# power.net
KiCad netlist of a schematic drawn in Altium Designer
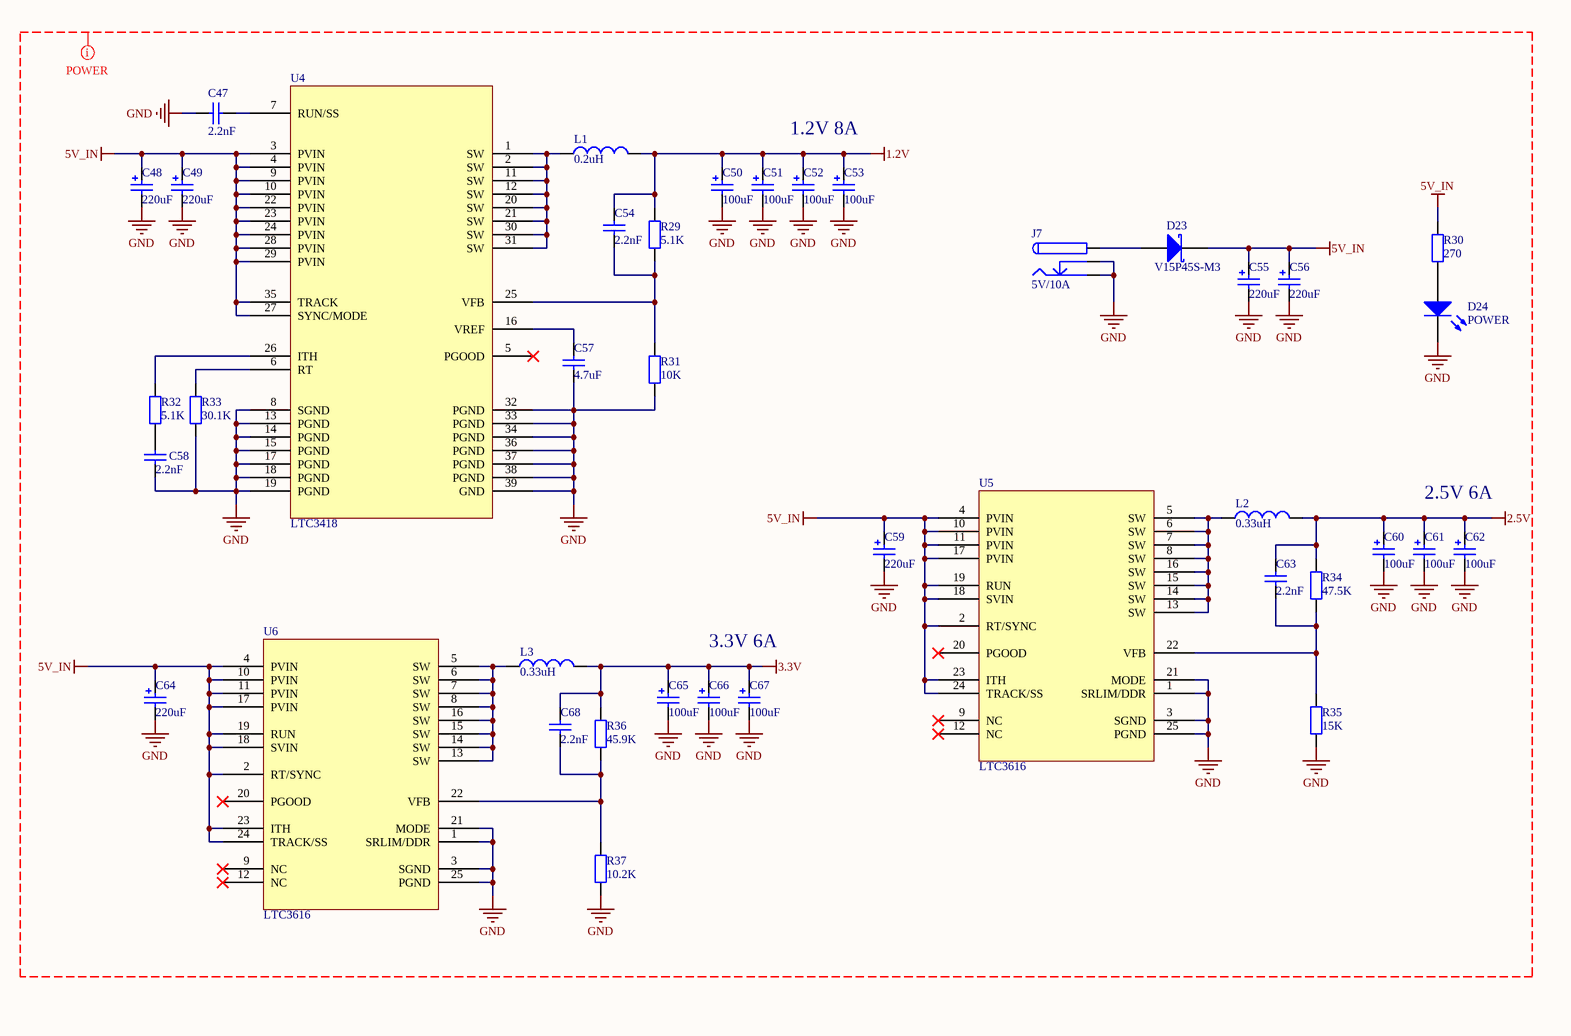
[diagram p0: power.SchDoc]

(export (version "E")
  (design (tool "Eeschema 10.0.6"))
  (components
    (comp (ref "C47")
      (value "2.2nF")
      (footprint "1608[0603]")
      (description "Capacitor")
      (fields (field (name "Comment") "Cap") (field (name "PUBLISHER") "Altium Limited"))
      (libsource (lib "Miscellaneous Devices") (part "Cap"))
    )
    (comp (ref "C48")
      (value "220uF")
      (footprint "C220_POLARIZED")
      (description "Polarized Capacitor (Axial)")
      (fields (field (name "Comment") "Cap Pol2") (field (name "PUBLISHER") "Altium Limited"))
      (libsource (lib "Miscellaneous Devices") (part "Cap Pol2"))
    )
    (comp (ref "C49")
      (value "220uF")
      (footprint "C220_POLARIZED")
      (description "Polarized Capacitor (Axial)")
      (fields (field (name "Comment") "Cap Pol2") (field (name "PUBLISHER") "Altium Limited"))
      (libsource (lib "Miscellaneous Devices") (part "Cap Pol2"))
    )
    (comp (ref "C50")
      (value "100uF")
      (footprint "C1206_POLARIZED")
      (description "Polarized Capacitor (Axial)")
      (fields (field (name "Comment") "Cap Pol2") (field (name "PUBLISHER") "Altium Limited"))
      (libsource (lib "Miscellaneous Devices") (part "Cap Pol2"))
    )
    (comp (ref "C51")
      (value "100uF")
      (footprint "C1206_POLARIZED")
      (description "Polarized Capacitor (Axial)")
      (fields (field (name "Comment") "Cap Pol2") (field (name "PUBLISHER") "Altium Limited"))
      (libsource (lib "Miscellaneous Devices") (part "Cap Pol2"))
    )
    (comp (ref "C52")
      (value "100uF")
      (footprint "C1206_POLARIZED")
      (description "Polarized Capacitor (Axial)")
      (fields (field (name "Comment") "Cap Pol2") (field (name "PUBLISHER") "Altium Limited"))
      (libsource (lib "Miscellaneous Devices") (part "Cap Pol2"))
    )
    (comp (ref "C53")
      (value "100uF")
      (footprint "C1206_POLARIZED")
      (description "Polarized Capacitor (Axial)")
      (fields (field (name "Comment") "Cap Pol2") (field (name "PUBLISHER") "Altium Limited"))
      (libsource (lib "Miscellaneous Devices") (part "Cap Pol2"))
    )
    (comp (ref "C54")
      (value "2.2nF")
      (footprint "1608[0603]")
      (description "Capacitor")
      (fields (field (name "Comment") "Cap") (field (name "PUBLISHER") "Altium Limited"))
      (libsource (lib "Miscellaneous Devices") (part "Cap"))
    )
    (comp (ref "C55")
      (value "220uF")
      (footprint "C220_POLARIZED")
      (description "Polarized Capacitor (Axial)")
      (fields (field (name "Comment") "Cap Pol2") (field (name "PUBLISHER") "Altium Limited"))
      (libsource (lib "Miscellaneous Devices") (part "Cap Pol2"))
    )
    (comp (ref "C56")
      (value "220uF")
      (footprint "C220_POLARIZED")
      (description "Polarized Capacitor (Axial)")
      (fields (field (name "Comment") "Cap Pol2") (field (name "PUBLISHER") "Altium Limited"))
      (libsource (lib "Miscellaneous Devices") (part "Cap Pol2"))
    )
    (comp (ref "C57")
      (value "4.7uF")
      (footprint "C0805")
      (description "Capacitor")
      (fields (field (name "Comment") "Cap") (field (name "PUBLISHER") "Altium Limited"))
      (libsource (lib "Miscellaneous Devices") (part "Cap"))
    )
    (comp (ref "C58")
      (value "2.2nF")
      (footprint "1608[0603]")
      (description "Capacitor")
      (fields (field (name "Comment") "Cap") (field (name "PUBLISHER") "Altium Limited"))
      (libsource (lib "Miscellaneous Devices") (part "Cap"))
    )
    (comp (ref "C59")
      (value "220uF")
      (footprint "C220_POLARIZED")
      (description "Polarized Capacitor (Axial)")
      (fields (field (name "Comment") "Cap Pol2") (field (name "PUBLISHER") "Altium Limited"))
      (libsource (lib "Miscellaneous Devices") (part "Cap Pol2"))
    )
    (comp (ref "C60")
      (value "100uF")
      (footprint "C1206_POLARIZED")
      (description "Polarized Capacitor (Axial)")
      (fields (field (name "Comment") "Cap Pol2") (field (name "PUBLISHER") "Altium Limited"))
      (libsource (lib "Miscellaneous Devices") (part "Cap Pol2"))
    )
    (comp (ref "C61")
      (value "100uF")
      (footprint "C1206_POLARIZED")
      (description "Polarized Capacitor (Axial)")
      (fields (field (name "Comment") "Cap Pol2") (field (name "PUBLISHER") "Altium Limited"))
      (libsource (lib "Miscellaneous Devices") (part "Cap Pol2"))
    )
    (comp (ref "C62")
      (value "100uF")
      (footprint "C1206_POLARIZED")
      (description "Polarized Capacitor (Axial)")
      (fields (field (name "Comment") "Cap Pol2") (field (name "PUBLISHER") "Altium Limited"))
      (libsource (lib "Miscellaneous Devices") (part "Cap Pol2"))
    )
    (comp (ref "C63")
      (value "2.2nF")
      (footprint "1608[0603]")
      (description "Capacitor")
      (fields (field (name "Comment") "Cap") (field (name "PUBLISHER") "Altium Limited"))
      (libsource (lib "Miscellaneous Devices") (part "Cap"))
    )
    (comp (ref "C64")
      (value "220uF")
      (footprint "C220_POLARIZED")
      (description "Polarized Capacitor (Axial)")
      (fields (field (name "Comment") "Cap Pol2") (field (name "PUBLISHER") "Altium Limited"))
      (libsource (lib "Miscellaneous Devices") (part "Cap Pol2"))
    )
    (comp (ref "C65")
      (value "100uF")
      (footprint "C1206_POLARIZED")
      (description "Polarized Capacitor (Axial)")
      (fields (field (name "Comment") "Cap Pol2") (field (name "PUBLISHER") "Altium Limited"))
      (libsource (lib "Miscellaneous Devices") (part "Cap Pol2"))
    )
    (comp (ref "C66")
      (value "100uF")
      (footprint "C1206_POLARIZED")
      (description "Polarized Capacitor (Axial)")
      (fields (field (name "Comment") "Cap Pol2") (field (name "PUBLISHER") "Altium Limited"))
      (libsource (lib "Miscellaneous Devices") (part "Cap Pol2"))
    )
    (comp (ref "C67")
      (value "100uF")
      (footprint "C1206_POLARIZED")
      (description "Polarized Capacitor (Axial)")
      (fields (field (name "Comment") "Cap Pol2") (field (name "PUBLISHER") "Altium Limited"))
      (libsource (lib "Miscellaneous Devices") (part "Cap Pol2"))
    )
    (comp (ref "C68")
      (value "2.2nF")
      (footprint "1608[0603]")
      (description "Capacitor")
      (fields (field (name "Comment") "Cap") (field (name "PUBLISHER") "Altium Limited"))
      (libsource (lib "Miscellaneous Devices") (part "Cap"))
    )
    (comp (ref "D23")
      (value "V15P45S-M3")
      (footprint "TO-227A")
      (description "Schottky Diode")
      (fields (field (name "PUBLISHER") "Altium Limited"))
      (libsource (lib "Miscellaneous Devices") (part "D Schottky"))
    )
    (comp (ref "D24")
      (value "POWER")
      (footprint "led")
      (description "Green")
      (fields (field (name "PUBLISHER") "Altium Limited"))
      (libsource (lib "Miscellaneous Devices") (part "LED3"))
    )
    (comp (ref "J7")
      (value "5V/10A")
      (footprint "DC_JACK")
      (description "Low Voltage Power Supply Connector")
      (fields (field (name "PUBLISHER") "Altium Limited"))
      (libsource (lib "Miscellaneous Connectors") (part "PWR2.5"))
    )
    (comp (ref "L1")
      (value "0.2uH")
      (footprint "INDP7367X100N")
      (description "Inductor")
      (fields (field (name "PUBLISHER") "Altium Limited"))
      (libsource (lib "Miscellaneous Devices") (part "Inductor"))
    )
    (comp (ref "L2")
      (value "0.33uH")
      (footprint "IHLP-2525CZ")
      (description "Inductor")
      (fields (field (name "PUBLISHER") "Altium Limited"))
      (libsource (lib "Miscellaneous Devices") (part "Inductor"))
    )
    (comp (ref "L3")
      (value "0.33uH")
      (footprint "IHLP-2525CZ")
      (description "Inductor")
      (fields (field (name "PUBLISHER") "Altium Limited"))
      (libsource (lib "Miscellaneous Devices") (part "Inductor"))
    )
    (comp (ref "R29")
      (value "5.1K")
      (footprint "J1-0603")
      (description "Resistor")
      (fields (field (name "Comment") "Res2") (field (name "PUBLISHER") "Altium Limited"))
      (libsource (lib "Miscellaneous Devices") (part "Res2"))
    )
    (comp (ref "R30")
      (value "270")
      (footprint "6-0805_N")
      (description "Resistor")
      (fields (field (name "Comment") "Res2") (field (name "PUBLISHER") "Altium Limited"))
      (libsource (lib "Miscellaneous Devices") (part "Res2"))
    )
    (comp (ref "R31")
      (value "10K")
      (footprint "J1-0603")
      (description "Resistor")
      (fields (field (name "Comment") "Res2") (field (name "PUBLISHER") "Altium Limited"))
      (libsource (lib "Miscellaneous Devices") (part "Res2"))
    )
    (comp (ref "R32")
      (value "5.1K")
      (footprint "J1-0603")
      (description "Resistor")
      (fields (field (name "Comment") "Res2") (field (name "PUBLISHER") "Altium Limited"))
      (libsource (lib "Miscellaneous Devices") (part "Res2"))
    )
    (comp (ref "R33")
      (value "30.1K")
      (footprint "J1-0603")
      (description "Resistor")
      (fields (field (name "Comment") "Res2") (field (name "PUBLISHER") "Altium Limited"))
      (libsource (lib "Miscellaneous Devices") (part "Res2"))
    )
    (comp (ref "R34")
      (value "47.5K")
      (footprint "J1-0603")
      (description "Resistor")
      (fields (field (name "Comment") "Res2") (field (name "PUBLISHER") "Altium Limited"))
      (libsource (lib "Miscellaneous Devices") (part "Res2"))
    )
    (comp (ref "R35")
      (value "15K")
      (footprint "J1-0603")
      (description "Resistor")
      (fields (field (name "Comment") "Res2") (field (name "PUBLISHER") "Altium Limited"))
      (libsource (lib "Miscellaneous Devices") (part "Res2"))
    )
    (comp (ref "R36")
      (value "45.9K")
      (footprint "J1-0603")
      (description "Resistor")
      (fields (field (name "Comment") "Res2") (field (name "PUBLISHER") "Altium Limited"))
      (libsource (lib "Miscellaneous Devices") (part "Res2"))
    )
    (comp (ref "R37")
      (value "10.2K")
      (footprint "J1-0603")
      (description "Resistor")
      (fields (field (name "Comment") "Res2") (field (name "PUBLISHER") "Altium Limited"))
      (libsource (lib "Miscellaneous Devices") (part "Res2"))
    )
    (comp (ref "U4") (value "LTC3418") (footprint "QFN38") (libsource (lib "FPGA_board") (part "LTC3418")))
    (comp (ref "U5")
      (value "LTC3616")
      (footprint "QFN24")
      (description "Step-Down, 6A, 4MHz")
      (libsource (lib "FPGA_board") (part "LTC3616"))
    )
    (comp (ref "U6")
      (value "LTC3616")
      (footprint "QFN24")
      (description "Step-Down, 6A, 4MHz")
      (libsource (lib "FPGA_board") (part "LTC3616"))
    )
  )
  (nets
    (net (code "1") (name "1.2V") (class "Default")
      (node (ref "C50") (pin "1") (pinfunction "1_1") (pintype "passive"))
      (node (ref "C51") (pin "1") (pinfunction "1_1") (pintype "passive"))
      (node (ref "C52") (pin "1") (pinfunction "1_1") (pintype "passive"))
      (node (ref "C53") (pin "1") (pinfunction "1_1") (pintype "passive"))
      (node (ref "C54") (pin "2") (pinfunction "2_2") (pintype "passive"))
      (node (ref "L1") (pin "2") (pinfunction "2_2") (pintype "passive"))
      (node (ref "R29") (pin "1") (pinfunction "1_1") (pintype "passive"))
    )
    (net (code "2") (name "2.5V") (class "Default")
      (node (ref "C60") (pin "1") (pinfunction "1_1") (pintype "passive"))
      (node (ref "C61") (pin "1") (pinfunction "1_1") (pintype "passive"))
      (node (ref "C62") (pin "1") (pinfunction "1_1") (pintype "passive"))
      (node (ref "C63") (pin "2") (pinfunction "2_2") (pintype "passive"))
      (node (ref "L2") (pin "2") (pinfunction "2_2") (pintype "passive"))
      (node (ref "R34") (pin "1") (pinfunction "1_1") (pintype "passive"))
    )
    (net (code "3") (name "3.3V") (class "Default")
      (node (ref "C65") (pin "1") (pinfunction "1_1") (pintype "passive"))
      (node (ref "C66") (pin "1") (pinfunction "1_1") (pintype "passive"))
      (node (ref "C67") (pin "1") (pinfunction "1_1") (pintype "passive"))
      (node (ref "C68") (pin "2") (pinfunction "2_2") (pintype "passive"))
      (node (ref "L3") (pin "2") (pinfunction "2_2") (pintype "passive"))
      (node (ref "R36") (pin "1") (pinfunction "1_1") (pintype "passive"))
    )
    (net (code "4") (name "5V_IN") (class "Default")
      (node (ref "C48") (pin "1") (pinfunction "1_1") (pintype "passive"))
      (node (ref "C49") (pin "1") (pinfunction "1_1") (pintype "passive"))
      (node (ref "C55") (pin "1") (pinfunction "1_1") (pintype "passive"))
      (node (ref "C56") (pin "1") (pinfunction "1_1") (pintype "passive"))
      (node (ref "C59") (pin "1") (pinfunction "1_1") (pintype "passive"))
      (node (ref "C64") (pin "1") (pinfunction "1_1") (pintype "passive"))
      (node (ref "D23") (pin "2") (pinfunction "K_2") (pintype "passive"))
      (node (ref "R30") (pin "1") (pinfunction "1_1") (pintype "passive"))
      (node (ref "U4") (pin "10") (pinfunction "PVIN_10") (pintype "passive"))
      (node (ref "U4") (pin "22") (pinfunction "PVIN_22") (pintype "passive"))
      (node (ref "U4") (pin "23") (pinfunction "PVIN_23") (pintype "passive"))
      (node (ref "U4") (pin "24") (pinfunction "PVIN_24") (pintype "passive"))
      (node (ref "U4") (pin "27") (pinfunction "SYNC/MODE_27") (pintype "passive"))
      (node (ref "U4") (pin "28") (pinfunction "PVIN_28") (pintype "passive"))
      (node (ref "U4") (pin "29") (pinfunction "PVIN_29") (pintype "passive"))
      (node (ref "U4") (pin "3") (pinfunction "PVIN_3") (pintype "passive"))
      (node (ref "U4") (pin "35") (pinfunction "TRACK_35") (pintype "passive"))
      (node (ref "U4") (pin "4") (pinfunction "PVIN_4") (pintype "passive"))
      (node (ref "U4") (pin "9") (pinfunction "PVIN_9") (pintype "passive"))
      (node (ref "U5") (pin "10") (pinfunction "PVIN_10") (pintype "passive"))
      (node (ref "U5") (pin "11") (pinfunction "PVIN_11") (pintype "passive"))
      (node (ref "U5") (pin "17") (pinfunction "PVIN_17") (pintype "passive"))
      (node (ref "U5") (pin "18") (pinfunction "SVIN_18") (pintype "passive"))
      (node (ref "U5") (pin "19") (pinfunction "RUN_19") (pintype "passive"))
      (node (ref "U5") (pin "2") (pinfunction "RT/SYNC_2") (pintype "passive"))
      (node (ref "U5") (pin "23") (pinfunction "ITH_23") (pintype "passive"))
      (node (ref "U5") (pin "24") (pinfunction "TRACK/SS_24") (pintype "passive"))
      (node (ref "U5") (pin "4") (pinfunction "PVIN_4") (pintype "passive"))
      (node (ref "U6") (pin "10") (pinfunction "PVIN_10") (pintype "passive"))
      (node (ref "U6") (pin "11") (pinfunction "PVIN_11") (pintype "passive"))
      (node (ref "U6") (pin "17") (pinfunction "PVIN_17") (pintype "passive"))
      (node (ref "U6") (pin "18") (pinfunction "SVIN_18") (pintype "passive"))
      (node (ref "U6") (pin "19") (pinfunction "RUN_19") (pintype "passive"))
      (node (ref "U6") (pin "2") (pinfunction "RT/SYNC_2") (pintype "passive"))
      (node (ref "U6") (pin "23") (pinfunction "ITH_23") (pintype "passive"))
      (node (ref "U6") (pin "24") (pinfunction "TRACK/SS_24") (pintype "passive"))
      (node (ref "U6") (pin "4") (pinfunction "PVIN_4") (pintype "passive"))
    )
    (net (code "5") (name "GND") (class "Default")
      (node (ref "C47") (pin "2") (pinfunction "2_2") (pintype "passive"))
      (node (ref "C48") (pin "2") (pinfunction "2_2") (pintype "passive"))
      (node (ref "C49") (pin "2") (pinfunction "2_2") (pintype "passive"))
      (node (ref "C50") (pin "2") (pinfunction "2_2") (pintype "passive"))
      (node (ref "C51") (pin "2") (pinfunction "2_2") (pintype "passive"))
      (node (ref "C52") (pin "2") (pinfunction "2_2") (pintype "passive"))
      (node (ref "C53") (pin "2") (pinfunction "2_2") (pintype "passive"))
      (node (ref "C55") (pin "2") (pinfunction "2_2") (pintype "passive"))
      (node (ref "C56") (pin "2") (pinfunction "2_2") (pintype "passive"))
      (node (ref "C57") (pin "1") (pinfunction "1_1") (pintype "passive"))
      (node (ref "C58") (pin "1") (pinfunction "1_1") (pintype "passive"))
      (node (ref "C59") (pin "2") (pinfunction "2_2") (pintype "passive"))
      (node (ref "C60") (pin "2") (pinfunction "2_2") (pintype "passive"))
      (node (ref "C61") (pin "2") (pinfunction "2_2") (pintype "passive"))
      (node (ref "C62") (pin "2") (pinfunction "2_2") (pintype "passive"))
      (node (ref "C64") (pin "2") (pinfunction "2_2") (pintype "passive"))
      (node (ref "C65") (pin "2") (pinfunction "2_2") (pintype "passive"))
      (node (ref "C66") (pin "2") (pinfunction "2_2") (pintype "passive"))
      (node (ref "C67") (pin "2") (pinfunction "2_2") (pintype "passive"))
      (node (ref "D24") (pin "2") (pinfunction "K_2") (pintype "passive"))
      (node (ref "J7") (pin "2") (pinfunction "2_2") (pintype "power_in"))
      (node (ref "J7") (pin "3") (pinfunction "3_3") (pintype "power_in"))
      (node (ref "R31") (pin "2") (pinfunction "2_2") (pintype "passive"))
      (node (ref "R33") (pin "2") (pinfunction "2_2") (pintype "passive"))
      (node (ref "R35") (pin "2") (pinfunction "2_2") (pintype "passive"))
      (node (ref "R37") (pin "2") (pinfunction "2_2") (pintype "passive"))
      (node (ref "U4") (pin "13") (pinfunction "PGND_13") (pintype "passive"))
      (node (ref "U4") (pin "14") (pinfunction "PGND_14") (pintype "passive"))
      (node (ref "U4") (pin "15") (pinfunction "PGND_15") (pintype "passive"))
      (node (ref "U4") (pin "17") (pinfunction "PGND_17") (pintype "passive"))
      (node (ref "U4") (pin "18") (pinfunction "PGND_18") (pintype "passive"))
      (node (ref "U4") (pin "19") (pinfunction "PGND_19") (pintype "passive"))
      (node (ref "U4") (pin "32") (pinfunction "PGND_32") (pintype "passive"))
      (node (ref "U4") (pin "33") (pinfunction "PGND_33") (pintype "passive"))
      (node (ref "U4") (pin "34") (pinfunction "PGND_34") (pintype "passive"))
      (node (ref "U4") (pin "36") (pinfunction "PGND_36") (pintype "passive"))
      (node (ref "U4") (pin "37") (pinfunction "PGND_37") (pintype "passive"))
      (node (ref "U4") (pin "38") (pinfunction "PGND_38") (pintype "passive"))
      (node (ref "U4") (pin "39") (pinfunction "GND_39") (pintype "passive"))
      (node (ref "U4") (pin "8") (pinfunction "SGND_8") (pintype "passive"))
      (node (ref "U5") (pin "1") (pinfunction "SRLIM/DDR_1") (pintype "passive"))
      (node (ref "U5") (pin "21") (pinfunction "MODE_21") (pintype "passive"))
      (node (ref "U5") (pin "25") (pinfunction "PGND_25") (pintype "passive"))
      (node (ref "U5") (pin "3") (pinfunction "SGND_3") (pintype "passive"))
      (node (ref "U6") (pin "1") (pinfunction "SRLIM/DDR_1") (pintype "passive"))
      (node (ref "U6") (pin "21") (pinfunction "MODE_21") (pintype "passive"))
      (node (ref "U6") (pin "25") (pinfunction "PGND_25") (pintype "passive"))
      (node (ref "U6") (pin "3") (pinfunction "SGND_3") (pintype "passive"))
    )
    (net (code "6") (name "Net-(C58-Pad2)") (class "Default")
      (node (ref "C58") (pin "2") (pinfunction "2_2") (pintype "passive"))
      (node (ref "R32") (pin "2") (pinfunction "2_2") (pintype "passive"))
    )
    (net (code "7") (name "Net-(D23-A)") (class "Default")
      (node (ref "D23") (pin "1") (pinfunction "A_1") (pintype "passive"))
      (node (ref "J7") (pin "1") (pinfunction "1_1") (pintype "power_in"))
    )
    (net (code "8") (name "Net-(D24-A)") (class "Default")
      (node (ref "D24") (pin "1") (pinfunction "A_1") (pintype "passive"))
      (node (ref "R30") (pin "2") (pinfunction "2_2") (pintype "passive"))
    )
    (net (code "9") (name "Net-(L1-Pad1)") (class "Default")
      (node (ref "L1") (pin "1") (pinfunction "1_1") (pintype "passive"))
      (node (ref "U4") (pin "1") (pinfunction "SW_1") (pintype "passive"))
      (node (ref "U4") (pin "11") (pinfunction "SW_11") (pintype "passive"))
      (node (ref "U4") (pin "12") (pinfunction "SW_12") (pintype "passive"))
      (node (ref "U4") (pin "2") (pinfunction "SW_2") (pintype "passive"))
      (node (ref "U4") (pin "20") (pinfunction "SW_20") (pintype "passive"))
      (node (ref "U4") (pin "21") (pinfunction "SW_21") (pintype "passive"))
      (node (ref "U4") (pin "30") (pinfunction "SW_30") (pintype "passive"))
      (node (ref "U4") (pin "31") (pinfunction "SW_31") (pintype "passive"))
    )
    (net (code "10") (name "Net-(L2-Pad1)") (class "Default")
      (node (ref "L2") (pin "1") (pinfunction "1_1") (pintype "passive"))
      (node (ref "U5") (pin "13") (pinfunction "SW_13") (pintype "passive"))
      (node (ref "U5") (pin "14") (pinfunction "SW_14") (pintype "passive"))
      (node (ref "U5") (pin "15") (pinfunction "SW_15") (pintype "passive"))
      (node (ref "U5") (pin "16") (pinfunction "SW_16") (pintype "passive"))
      (node (ref "U5") (pin "5") (pinfunction "SW_5") (pintype "passive"))
      (node (ref "U5") (pin "6") (pinfunction "SW_6") (pintype "passive"))
      (node (ref "U5") (pin "7") (pinfunction "SW_7") (pintype "passive"))
      (node (ref "U5") (pin "8") (pinfunction "SW_8") (pintype "passive"))
    )
    (net (code "11") (name "Net-(L3-Pad1)") (class "Default")
      (node (ref "L3") (pin "1") (pinfunction "1_1") (pintype "passive"))
      (node (ref "U6") (pin "13") (pinfunction "SW_13") (pintype "passive"))
      (node (ref "U6") (pin "14") (pinfunction "SW_14") (pintype "passive"))
      (node (ref "U6") (pin "15") (pinfunction "SW_15") (pintype "passive"))
      (node (ref "U6") (pin "16") (pinfunction "SW_16") (pintype "passive"))
      (node (ref "U6") (pin "5") (pinfunction "SW_5") (pintype "passive"))
      (node (ref "U6") (pin "6") (pinfunction "SW_6") (pintype "passive"))
      (node (ref "U6") (pin "7") (pinfunction "SW_7") (pintype "passive"))
      (node (ref "U6") (pin "8") (pinfunction "SW_8") (pintype "passive"))
    )
    (net (code "12") (name "Net-(U4-ITH)") (class "Default")
      (node (ref "R32") (pin "1") (pinfunction "1_1") (pintype "passive"))
      (node (ref "U4") (pin "26") (pinfunction "ITH_26") (pintype "passive"))
    )
    (net (code "13") (name "Net-(U4-RT)") (class "Default")
      (node (ref "R33") (pin "1") (pinfunction "1_1") (pintype "passive"))
      (node (ref "U4") (pin "6") (pinfunction "RT_6") (pintype "passive"))
    )
    (net (code "14") (name "Net-(U4-RUN{slash}SS)") (class "Default")
      (node (ref "C47") (pin "1") (pinfunction "1_1") (pintype "passive"))
      (node (ref "U4") (pin "7") (pinfunction "RUN/SS_7") (pintype "passive"))
    )
    (net (code "15") (name "Net-(U4-VFB)") (class "Default")
      (node (ref "C54") (pin "1") (pinfunction "1_1") (pintype "passive"))
      (node (ref "R29") (pin "2") (pinfunction "2_2") (pintype "passive"))
      (node (ref "R31") (pin "1") (pinfunction "1_1") (pintype "passive"))
      (node (ref "U4") (pin "25") (pinfunction "VFB_25") (pintype "passive"))
    )
    (net (code "16") (name "Net-(U4-VREF)") (class "Default")
      (node (ref "C57") (pin "2") (pinfunction "2_2") (pintype "passive"))
      (node (ref "U4") (pin "16") (pinfunction "VREF_16") (pintype "passive"))
    )
    (net (code "17") (name "Net-(U5-VFB)") (class "Default")
      (node (ref "C63") (pin "1") (pinfunction "1_1") (pintype "passive"))
      (node (ref "R34") (pin "2") (pinfunction "2_2") (pintype "passive"))
      (node (ref "R35") (pin "1") (pinfunction "1_1") (pintype "passive"))
      (node (ref "U5") (pin "22") (pinfunction "VFB_22") (pintype "passive"))
    )
    (net (code "18") (name "Net-(U6-VFB)") (class "Default")
      (node (ref "C68") (pin "1") (pinfunction "1_1") (pintype "passive"))
      (node (ref "R36") (pin "2") (pinfunction "2_2") (pintype "passive"))
      (node (ref "R37") (pin "1") (pinfunction "1_1") (pintype "passive"))
      (node (ref "U6") (pin "22") (pinfunction "VFB_22") (pintype "passive"))
    )
    (net (code "19") (name "unconnected-(U4-PGOOD-Pad5)") (class "Default")
      (node (ref "U4") (pin "5") (pinfunction "PGOOD_5") (pintype "passive+no_connect"))
    )
    (net (code "20") (name "unconnected-(U5-NC-Pad9)") (class "Default")
      (node (ref "U5") (pin "9") (pinfunction "NC_9") (pintype "passive+no_connect"))
    )
    (net (code "21") (name "unconnected-(U5-NC-Pad12)") (class "Default")
      (node (ref "U5") (pin "12") (pinfunction "NC_12") (pintype "passive+no_connect"))
    )
    (net (code "22") (name "unconnected-(U5-PGOOD-Pad20)") (class "Default")
      (node (ref "U5") (pin "20") (pinfunction "PGOOD_20") (pintype "passive+no_connect"))
    )
    (net (code "23") (name "unconnected-(U6-NC-Pad9)") (class "Default")
      (node (ref "U6") (pin "9") (pinfunction "NC_9") (pintype "passive+no_connect"))
    )
    (net (code "24") (name "unconnected-(U6-NC-Pad12)") (class "Default")
      (node (ref "U6") (pin "12") (pinfunction "NC_12") (pintype "passive+no_connect"))
    )
    (net (code "25") (name "unconnected-(U6-PGOOD-Pad20)") (class "Default")
      (node (ref "U6") (pin "20") (pinfunction "PGOOD_20") (pintype "passive+no_connect"))
    )
  )
)
